# power.net
KiCad netlist of a schematic drawn in EAGLE
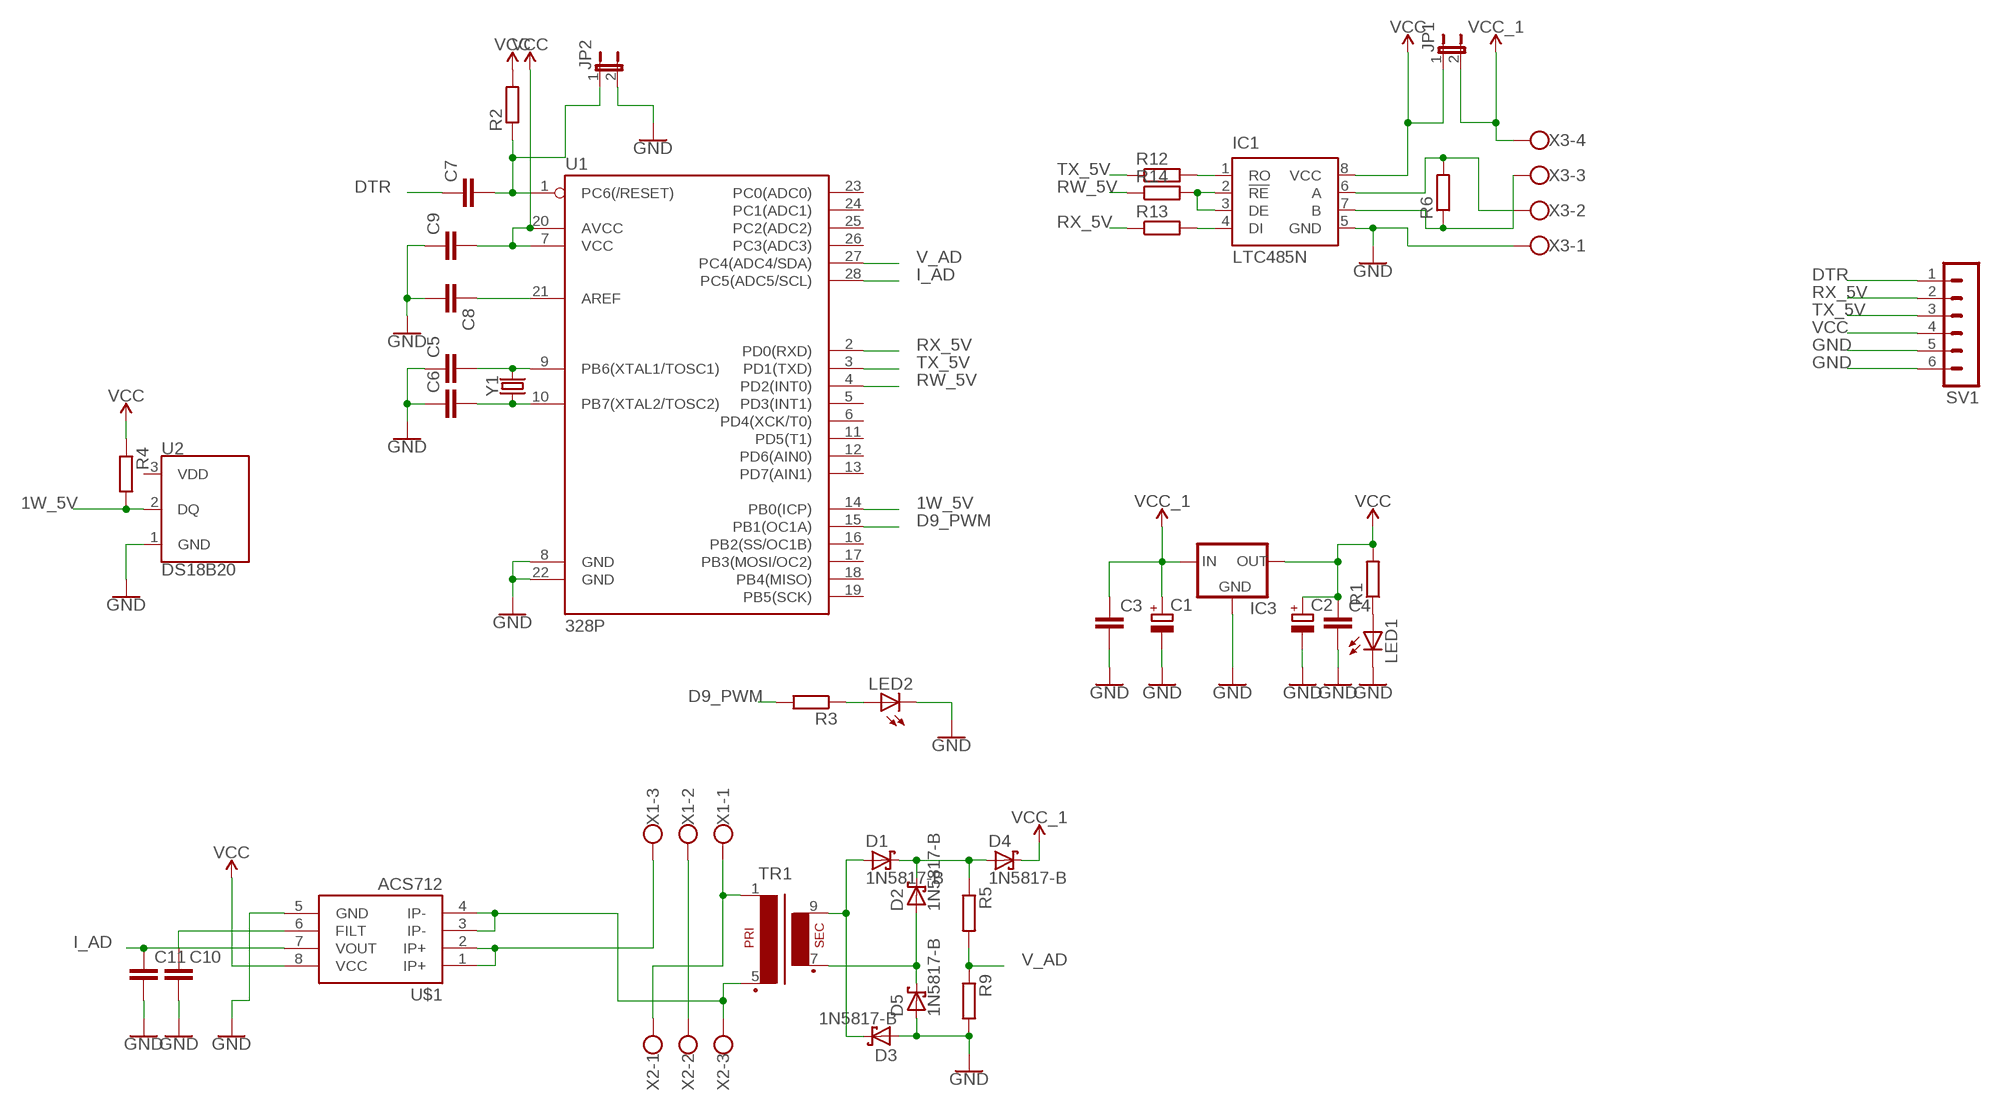
[diagram p0: schematic, sheet 1]

(export (version "E")
  (design (tool "Eeschema 10.0.6"))
  (components
    (comp (ref "C1")
      (value "CPOL-EUE5-10.5")
      (footprint "eagle-import:E5-10,5")
      (libsource (lib "eagle-import") (part "CPOL-EUE5-10.5"))
    )
    (comp (ref "C2")
      (value "CPOL-EUE5-10.5")
      (footprint "eagle-import:E5-10,5")
      (libsource (lib "eagle-import") (part "CPOL-EUE5-10.5"))
    )
    (comp (ref "C3")
      (value "C-EU025-025X050")
      (footprint "eagle-import:C025-025X050")
      (libsource (lib "eagle-import") (part "C-EU025-025X050"))
    )
    (comp (ref "C4")
      (value "C-EU025-025X050")
      (footprint "eagle-import:C025-025X050")
      (libsource (lib "eagle-import") (part "C-EU025-025X050"))
    )
    (comp (ref "C5")
      (value "C-EU025-025X050")
      (footprint "eagle-import:C025-025X050")
      (libsource (lib "eagle-import") (part "C-EU025-025X050"))
    )
    (comp (ref "C6")
      (value "C-EU025-025X050")
      (footprint "eagle-import:C025-025X050")
      (libsource (lib "eagle-import") (part "C-EU025-025X050"))
    )
    (comp (ref "C7")
      (value "C-EU025-025X050")
      (footprint "eagle-import:C025-025X050")
      (libsource (lib "eagle-import") (part "C-EU025-025X050"))
    )
    (comp (ref "C8")
      (value "C-EU025-025X050")
      (footprint "eagle-import:C025-025X050")
      (libsource (lib "eagle-import") (part "C-EU025-025X050"))
    )
    (comp (ref "C9")
      (value "C-EU025-025X050")
      (footprint "eagle-import:C025-025X050")
      (libsource (lib "eagle-import") (part "C-EU025-025X050"))
    )
    (comp (ref "C10")
      (value "C-EU025-025X050")
      (footprint "eagle-import:C025-025X050")
      (libsource (lib "eagle-import") (part "C-EU025-025X050"))
    )
    (comp (ref "C11")
      (value "C-EU025-025X050")
      (footprint "eagle-import:C025-025X050")
      (libsource (lib "eagle-import") (part "C-EU025-025X050"))
    )
    (comp (ref "D1")
      (value "1N5817-B")
      (footprint "eagle-import:DO41-7.6")
      (libsource (lib "eagle-import") (part "1N5817-B"))
    )
    (comp (ref "D2")
      (value "1N5817-B")
      (footprint "eagle-import:DO41-7.6")
      (libsource (lib "eagle-import") (part "1N5817-B"))
    )
    (comp (ref "D3")
      (value "1N5817-B")
      (footprint "eagle-import:DO41-7.6")
      (libsource (lib "eagle-import") (part "1N5817-B"))
    )
    (comp (ref "D4")
      (value "1N5817-B")
      (footprint "eagle-import:DO41-7.6")
      (libsource (lib "eagle-import") (part "1N5817-B"))
    )
    (comp (ref "D5")
      (value "1N5817-B")
      (footprint "eagle-import:DO41-7.6")
      (libsource (lib "eagle-import") (part "1N5817-B"))
    )
    (comp (ref "IC1")
      (value "LTC485N")
      (footprint "eagle-import:DIL08")
      (libsource (lib "eagle-import") (part "LTC485N"))
    )
    (comp (ref "IC3")
      (value "78XXL")
      (footprint "eagle-import:78XXL")
      (libsource (lib "eagle-import") (part "78XXL"))
    )
    (comp (ref "JP1")
      (value "JP1E")
      (footprint "eagle-import:JP1")
      (libsource (lib "eagle-import") (part "JP1E"))
    )
    (comp (ref "JP2")
      (value "JP1E")
      (footprint "eagle-import:JP1")
      (libsource (lib "eagle-import") (part "JP1E"))
    )
    (comp (ref "LED1")
      (value "LED5MM")
      (footprint "eagle-import:LED5MM")
      (libsource (lib "eagle-import") (part "LED5MM"))
    )
    (comp (ref "LED2")
      (value "LED5MM")
      (footprint "eagle-import:LED5MM")
      (libsource (lib "eagle-import") (part "LED5MM"))
    )
    (comp (ref "R1")
      (value "R-EU_0204/7")
      (footprint "eagle-import:0204_7")
      (libsource (lib "eagle-import") (part "R-EU_0204/7"))
    )
    (comp (ref "R2")
      (value "R-EU_0204/7")
      (footprint "eagle-import:0204_7")
      (libsource (lib "eagle-import") (part "R-EU_0204/7"))
    )
    (comp (ref "R3")
      (value "R-EU_0204/7")
      (footprint "eagle-import:0204_7")
      (libsource (lib "eagle-import") (part "R-EU_0204/7"))
    )
    (comp (ref "R4")
      (value "R-EU_0204/7")
      (footprint "eagle-import:0204_7")
      (libsource (lib "eagle-import") (part "R-EU_0204/7"))
    )
    (comp (ref "R5")
      (value "R-EU_0204/7")
      (footprint "eagle-import:0204_7")
      (libsource (lib "eagle-import") (part "R-EU_0204/7"))
    )
    (comp (ref "R6")
      (value "R-EU_0204/7")
      (footprint "eagle-import:0204_7")
      (libsource (lib "eagle-import") (part "R-EU_0204/7"))
    )
    (comp (ref "R9")
      (value "R-EU_0204/7")
      (footprint "eagle-import:0204_7")
      (libsource (lib "eagle-import") (part "R-EU_0204/7"))
    )
    (comp (ref "R12")
      (value "R-EU_0204/7")
      (footprint "eagle-import:0204_7")
      (libsource (lib "eagle-import") (part "R-EU_0204/7"))
    )
    (comp (ref "R13")
      (value "R-EU_0204/7")
      (footprint "eagle-import:0204_7")
      (libsource (lib "eagle-import") (part "R-EU_0204/7"))
    )
    (comp (ref "R14")
      (value "R-EU_0204/7")
      (footprint "eagle-import:0204_7")
      (libsource (lib "eagle-import") (part "R-EU_0204/7"))
    )
    (comp (ref "SV1")
      (value "MA06-1")
      (footprint "eagle-import:MA06-1")
      (libsource (lib "eagle-import") (part "MA06-1"))
    )
    (comp (ref "TR1")
      (value "EI30-1")
      (footprint "eagle-import:EI30-1")
      (libsource (lib "eagle-import") (part "EI30-1"))
    )
    (comp (ref "U$1")
      (value "ACS712")
      (footprint "eagle-import:SO08")
      (libsource (lib "eagle-import") (part "ACS712"))
    )
    (comp (ref "U1")
      (value "328P")
      (footprint "eagle-import:DIP28")
      (libsource (lib "eagle-import") (part "ATMEGA328P_PDIP"))
    )
    (comp (ref "U2")
      (value "DS18B20")
      (footprint "eagle-import:TO-92-AMMO")
      (libsource (lib "eagle-import") (part "DS18B20"))
    )
    (comp (ref "X1")
      (value "W237-103")
      (footprint "eagle-import:W237-103")
      (fields (field (name "MPN") "237-103"))
      (libsource (lib "eagle-import") (part "W237-103"))
    )
    (comp (ref "X2")
      (value "W237-103")
      (footprint "eagle-import:W237-103")
      (fields (field (name "MPN") "237-103"))
      (libsource (lib "eagle-import") (part "W237-103"))
    )
    (comp (ref "X3")
      (value "W237-4")
      (footprint "eagle-import:W237-4")
      (libsource (lib "eagle-import") (part "W237-4"))
    )
    (comp (ref "Y1")
      (value "CRYSTALPTH-HC49US")
      (footprint "eagle-import:HC49US")
      (libsource (lib "eagle-import") (part "CRYSTALPTH-HC49US"))
    )
  )
  (nets
    (net (code "1") (name "/1W_5V") (class "Default")
      (node (ref "R4") (pin "2") (pinfunction "2_2") (pintype "passive"))
      (node (ref "U1") (pin "14") (pinfunction "PB0(ICP)_14") (pintype "bidirectional"))
      (node (ref "U2") (pin "2") (pinfunction "DQ_2") (pintype "bidirectional"))
    )
    (net (code "2") (name "/D9_PWM") (class "Default")
      (node (ref "R3") (pin "2") (pinfunction "2_2") (pintype "passive"))
      (node (ref "U1") (pin "15") (pinfunction "PB1(OC1A)_15") (pintype "bidirectional"))
    )
    (net (code "3") (name "/DTR") (class "Default")
      (node (ref "C7") (pin "1") (pinfunction "1_1") (pintype "passive"))
      (node (ref "SV1") (pin "1") (pinfunction "1_1") (pintype "passive"))
    )
    (net (code "4") (name "/I_AD") (class "Default")
      (node (ref "C11") (pin "1") (pinfunction "1_1") (pintype "passive"))
      (node (ref "U$1") (pin "7") (pinfunction "VOUT_7") (pintype "bidirectional"))
      (node (ref "U1") (pin "28") (pinfunction "PC5(ADC5/SCL)_28") (pintype "bidirectional"))
    )
    (net (code "5") (name "/RW_5V") (class "Default")
      (node (ref "R14") (pin "1") (pinfunction "1_1") (pintype "passive"))
      (node (ref "U1") (pin "4") (pinfunction "PD2(INT0)_4") (pintype "bidirectional"))
    )
    (net (code "6") (name "/RX_5V") (class "Default")
      (node (ref "R13") (pin "1") (pinfunction "1_1") (pintype "passive"))
      (node (ref "SV1") (pin "2") (pinfunction "2_2") (pintype "passive"))
      (node (ref "U1") (pin "2") (pinfunction "PD0(RXD)_2") (pintype "bidirectional"))
    )
    (net (code "7") (name "/TX_5V") (class "Default")
      (node (ref "R12") (pin "1") (pinfunction "1_1") (pintype "passive"))
      (node (ref "SV1") (pin "3") (pinfunction "3_3") (pintype "passive"))
      (node (ref "U1") (pin "3") (pinfunction "PD1(TXD)_3") (pintype "bidirectional"))
    )
    (net (code "8") (name "/VDD") (class "Default")
      (node (ref "U2") (pin "3") (pinfunction "VDD_3") (pintype "power_in"))
    )
    (net (code "9") (name "/V_AD") (class "Default")
      (node (ref "R5") (pin "2") (pinfunction "2_2") (pintype "passive"))
      (node (ref "R9") (pin "1") (pinfunction "1_1") (pintype "passive"))
      (node (ref "U1") (pin "27") (pinfunction "PC4(ADC4/SDA)_27") (pintype "bidirectional"))
    )
    (net (code "10") (name "GND") (class "Default")
      (node (ref "C1") (pin "-") (pinfunction "-_-") (pintype "passive"))
      (node (ref "C10") (pin "2") (pinfunction "2_2") (pintype "passive"))
      (node (ref "C11") (pin "2") (pinfunction "2_2") (pintype "passive"))
      (node (ref "C2") (pin "-") (pinfunction "-_-") (pintype "passive"))
      (node (ref "C3") (pin "2") (pinfunction "2_2") (pintype "passive"))
      (node (ref "C4") (pin "2") (pinfunction "2_2") (pintype "passive"))
      (node (ref "C5") (pin "1") (pinfunction "1_1") (pintype "passive"))
      (node (ref "C6") (pin "1") (pinfunction "1_1") (pintype "passive"))
      (node (ref "C8") (pin "2") (pinfunction "2_2") (pintype "passive"))
      (node (ref "C9") (pin "1") (pinfunction "1_1") (pintype "passive"))
      (node (ref "D3") (pin "A") (pinfunction "A_A") (pintype "passive"))
      (node (ref "D5") (pin "A") (pinfunction "A_A") (pintype "passive"))
      (node (ref "IC1") (pin "5") (pinfunction "GND_5") (pintype "input"))
      (node (ref "IC3") (pin "GND") (pinfunction "GND_GND") (pintype "input"))
      (node (ref "JP2") (pin "2") (pinfunction "2_2") (pintype "passive"))
      (node (ref "LED1") (pin "K") (pinfunction "C_K") (pintype "passive"))
      (node (ref "LED2") (pin "K") (pinfunction "C_K") (pintype "passive"))
      (node (ref "R9") (pin "2") (pinfunction "2_2") (pintype "passive"))
      (node (ref "SV1") (pin "5") (pinfunction "5_5") (pintype "passive"))
      (node (ref "SV1") (pin "6") (pinfunction "6_6") (pintype "passive"))
      (node (ref "U$1") (pin "5") (pinfunction "GND_5") (pintype "bidirectional"))
      (node (ref "U1") (pin "22") (pinfunction "GND_22") (pintype "bidirectional"))
      (node (ref "U1") (pin "8") (pinfunction "GND_8") (pintype "bidirectional"))
      (node (ref "U2") (pin "1") (pinfunction "GND_1") (pintype "power_in"))
      (node (ref "X3") (pin "1") (pinfunction "KL_1") (pintype "passive"))
    )
    (net (code "11") (name "Net-(D1-PadC)") (class "Default")
      (node (ref "D1") (pin "C") (pinfunction "C_C") (pintype "passive"))
      (node (ref "D2") (pin "C") (pinfunction "C_C") (pintype "passive"))
      (node (ref "D4") (pin "A") (pinfunction "A_A") (pintype "passive"))
      (node (ref "R5") (pin "1") (pinfunction "1_1") (pintype "passive"))
    )
    (net (code "12") (name "Net-(IC1-A)") (class "Default")
      (node (ref "IC1") (pin "6") (pinfunction "A_6") (pintype "bidirectional"))
      (node (ref "R6") (pin "2") (pinfunction "2_2") (pintype "passive"))
      (node (ref "X3") (pin "2") (pinfunction "KL_2") (pintype "passive"))
    )
    (net (code "13") (name "Net-(IC1-B)") (class "Default")
      (node (ref "IC1") (pin "7") (pinfunction "B_7") (pintype "bidirectional"))
      (node (ref "R6") (pin "1") (pinfunction "1_1") (pintype "passive"))
      (node (ref "X3") (pin "3") (pinfunction "KL_3") (pintype "passive"))
    )
    (net (code "14") (name "Net-(IC1-DE)") (class "Default")
      (node (ref "IC1") (pin "2") (pinfunction "~{RE}_2") (pintype "input"))
      (node (ref "IC1") (pin "3") (pinfunction "DE_3") (pintype "input"))
      (node (ref "R14") (pin "2") (pinfunction "2_2") (pintype "passive"))
    )
    (net (code "15") (name "Net-(IC1-DI)") (class "Default")
      (node (ref "IC1") (pin "4") (pinfunction "DI_4") (pintype "input"))
      (node (ref "R13") (pin "2") (pinfunction "2_2") (pintype "passive"))
    )
    (net (code "16") (name "Net-(IC1-RO)") (class "Default")
      (node (ref "IC1") (pin "1") (pinfunction "RO_1") (pintype "output"))
      (node (ref "R12") (pin "2") (pinfunction "2_2") (pintype "passive"))
    )
    (net (code "17") (name "Net-(LED1-PadA)") (class "Default")
      (node (ref "LED1") (pin "A") (pinfunction "A_A") (pintype "passive"))
      (node (ref "R1") (pin "1") (pinfunction "1_1") (pintype "passive"))
    )
    (net (code "18") (name "Net-(LED2-PadA)") (class "Default")
      (node (ref "LED2") (pin "A") (pinfunction "A_A") (pintype "passive"))
      (node (ref "R3") (pin "1") (pinfunction "1_1") (pintype "passive"))
    )
    (net (code "19") (name "Net-(TR1-P1)") (class "Default")
      (node (ref "TR1") (pin "1") (pinfunction "P1_1") (pintype "passive"))
      (node (ref "X1") (pin "1") (pinfunction "KL_1") (pintype "passive"))
      (node (ref "X2") (pin "1") (pinfunction "KL_1") (pintype "passive"))
    )
    (net (code "20") (name "Net-(TR1-P2)") (class "Default")
      (node (ref "TR1") (pin "5") (pinfunction "P2_5") (pintype "passive"))
      (node (ref "U$1") (pin "3") (pinfunction "IP-_3") (pintype "bidirectional"))
      (node (ref "U$1") (pin "4") (pinfunction "IP-_4") (pintype "bidirectional"))
      (node (ref "X2") (pin "3") (pinfunction "KL_3") (pintype "passive"))
    )
    (net (code "21") (name "Net-(TR1-S3)") (class "Default")
      (node (ref "D2") (pin "A") (pinfunction "A_A") (pintype "passive"))
      (node (ref "D5") (pin "C") (pinfunction "C_C") (pintype "passive"))
      (node (ref "TR1") (pin "7") (pinfunction "S3_7") (pintype "passive"))
    )
    (net (code "22") (name "Net-(TR1-S4)") (class "Default")
      (node (ref "D1") (pin "A") (pinfunction "A_A") (pintype "passive"))
      (node (ref "D3") (pin "C") (pinfunction "C_C") (pintype "passive"))
      (node (ref "TR1") (pin "9") (pinfunction "S4_9") (pintype "passive"))
    )
    (net (code "23") (name "Net-(U$1-FILT)") (class "Default")
      (node (ref "C10") (pin "1") (pinfunction "1_1") (pintype "passive"))
      (node (ref "U$1") (pin "6") (pinfunction "FILT_6") (pintype "bidirectional"))
    )
    (net (code "24") (name "Net-(U1-AREF)") (class "Default")
      (node (ref "C8") (pin "1") (pinfunction "1_1") (pintype "passive"))
      (node (ref "U1") (pin "21") (pinfunction "AREF_21") (pintype "bidirectional"))
    )
    (net (code "25") (name "Net-(U1-PB6(XTAL1{slash}TOSC1))") (class "Default")
      (node (ref "C5") (pin "2") (pinfunction "2_2") (pintype "passive"))
      (node (ref "U1") (pin "9") (pinfunction "PB6(XTAL1/TOSC1)_9") (pintype "bidirectional"))
      (node (ref "Y1") (pin "2") (pinfunction "2_2") (pintype "passive"))
    )
    (net (code "26") (name "Net-(U1-PB7(XTAL2{slash}TOSC2))") (class "Default")
      (node (ref "C6") (pin "2") (pinfunction "2_2") (pintype "passive"))
      (node (ref "U1") (pin "10") (pinfunction "PB7(XTAL2/TOSC2)_10") (pintype "bidirectional"))
      (node (ref "Y1") (pin "1") (pinfunction "1_1") (pintype "passive"))
    )
    (net (code "27") (name "Net-(U1-PC6({slash}RESET))") (class "Default")
      (node (ref "C7") (pin "2") (pinfunction "2_2") (pintype "passive"))
      (node (ref "JP2") (pin "1") (pinfunction "1_1") (pintype "passive"))
      (node (ref "R2") (pin "1") (pinfunction "1_1") (pintype "passive"))
      (node (ref "U1") (pin "1") (pinfunction "PC6(/RESET)_1") (pintype "bidirectional"))
    )
    (net (code "28") (name "Net-(X1B-KL)") (class "Default")
      (node (ref "X1") (pin "2") (pinfunction "KL_2") (pintype "passive"))
      (node (ref "X2") (pin "2") (pinfunction "KL_2") (pintype "passive"))
    )
    (net (code "29") (name "Net-(X1C-KL)") (class "Default")
      (node (ref "U$1") (pin "1") (pinfunction "IP+_1") (pintype "bidirectional"))
      (node (ref "U$1") (pin "2") (pinfunction "IP+_2") (pintype "bidirectional"))
      (node (ref "X1") (pin "3") (pinfunction "KL_3") (pintype "passive"))
    )
    (net (code "30") (name "VCC") (class "Default")
      (node (ref "C2") (pin "+") (pinfunction "+_+") (pintype "passive"))
      (node (ref "C4") (pin "1") (pinfunction "1_1") (pintype "passive"))
      (node (ref "C9") (pin "2") (pinfunction "2_2") (pintype "passive"))
      (node (ref "IC1") (pin "8") (pinfunction "VCC_8") (pintype "input"))
      (node (ref "IC3") (pin "OUT") (pinfunction "OUT_OUT") (pintype "passive"))
      (node (ref "JP1") (pin "1") (pinfunction "1_1") (pintype "passive"))
      (node (ref "R1") (pin "2") (pinfunction "2_2") (pintype "passive"))
      (node (ref "R2") (pin "2") (pinfunction "2_2") (pintype "passive"))
      (node (ref "R4") (pin "1") (pinfunction "1_1") (pintype "passive"))
      (node (ref "SV1") (pin "4") (pinfunction "4_4") (pintype "passive"))
      (node (ref "U$1") (pin "8") (pinfunction "VCC_8") (pintype "bidirectional"))
      (node (ref "U1") (pin "20") (pinfunction "AVCC_20") (pintype "bidirectional"))
      (node (ref "U1") (pin "7") (pinfunction "VCC_7") (pintype "bidirectional"))
    )
    (net (code "31") (name "VCC_1") (class "Default")
      (node (ref "C1") (pin "+") (pinfunction "+_+") (pintype "passive"))
      (node (ref "C3") (pin "1") (pinfunction "1_1") (pintype "passive"))
      (node (ref "D4") (pin "C") (pinfunction "C_C") (pintype "passive"))
      (node (ref "IC3") (pin "IN") (pinfunction "IN_IN") (pintype "input"))
      (node (ref "JP1") (pin "2") (pinfunction "2_2") (pintype "passive"))
      (node (ref "X3") (pin "4") (pinfunction "KL_4") (pintype "passive"))
    )
    (net (code "32") (name "unconnected-(U1-PB2(SS{slash}OC1B)-Pad16)") (class "Default")
      (node (ref "U1") (pin "16") (pinfunction "PB2(SS/OC1B)_16") (pintype "bidirectional"))
    )
    (net (code "33") (name "unconnected-(U1-PB3(MOSI{slash}OC2)-Pad17)") (class "Default")
      (node (ref "U1") (pin "17") (pinfunction "PB3(MOSI/OC2)_17") (pintype "bidirectional"))
    )
    (net (code "34") (name "unconnected-(U1-PB4(MISO)-Pad18)") (class "Default")
      (node (ref "U1") (pin "18") (pinfunction "PB4(MISO)_18") (pintype "bidirectional"))
    )
    (net (code "35") (name "unconnected-(U1-PB5(SCK)-Pad19)") (class "Default")
      (node (ref "U1") (pin "19") (pinfunction "PB5(SCK)_19") (pintype "bidirectional"))
    )
    (net (code "36") (name "unconnected-(U1-PC0(ADC0)-Pad23)") (class "Default")
      (node (ref "U1") (pin "23") (pinfunction "PC0(ADC0)_23") (pintype "bidirectional"))
    )
    (net (code "37") (name "unconnected-(U1-PC1(ADC1)-Pad24)") (class "Default")
      (node (ref "U1") (pin "24") (pinfunction "PC1(ADC1)_24") (pintype "bidirectional"))
    )
    (net (code "38") (name "unconnected-(U1-PC2(ADC2)-Pad25)") (class "Default")
      (node (ref "U1") (pin "25") (pinfunction "PC2(ADC2)_25") (pintype "bidirectional"))
    )
    (net (code "39") (name "unconnected-(U1-PC3(ADC3)-Pad26)") (class "Default")
      (node (ref "U1") (pin "26") (pinfunction "PC3(ADC3)_26") (pintype "bidirectional"))
    )
    (net (code "40") (name "unconnected-(U1-PD3(INT1)-Pad5)") (class "Default")
      (node (ref "U1") (pin "5") (pinfunction "PD3(INT1)_5") (pintype "bidirectional"))
    )
    (net (code "41") (name "unconnected-(U1-PD4(XCK{slash}T0)-Pad6)") (class "Default")
      (node (ref "U1") (pin "6") (pinfunction "PD4(XCK/T0)_6") (pintype "bidirectional"))
    )
    (net (code "42") (name "unconnected-(U1-PD5(T1)-Pad11)") (class "Default")
      (node (ref "U1") (pin "11") (pinfunction "PD5(T1)_11") (pintype "bidirectional"))
    )
    (net (code "43") (name "unconnected-(U1-PD6(AIN0)-Pad12)") (class "Default")
      (node (ref "U1") (pin "12") (pinfunction "PD6(AIN0)_12") (pintype "bidirectional"))
    )
    (net (code "44") (name "unconnected-(U1-PD7(AIN1)-Pad13)") (class "Default")
      (node (ref "U1") (pin "13") (pinfunction "PD7(AIN1)_13") (pintype "bidirectional"))
    )
  )
)
